# Sheet1.net
KiCad netlist of a schematic drawn in Altium Designer
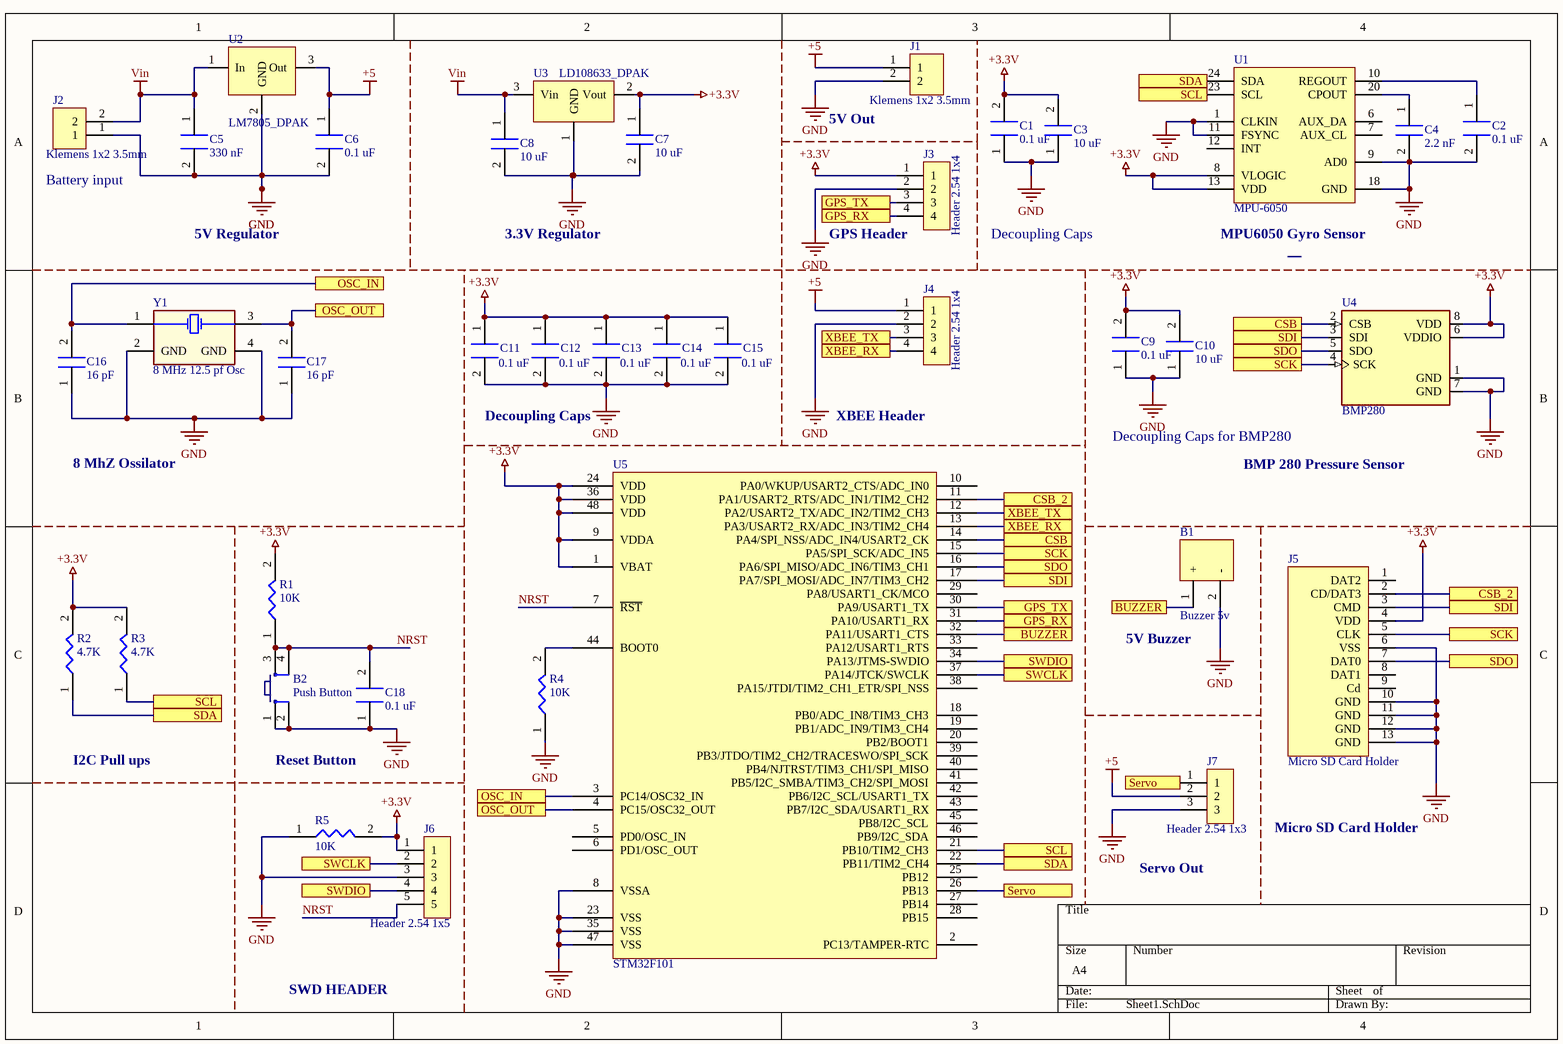
[diagram p0: Sheet1.SchDoc]

(export (version "E")
  (design (tool "Eeschema 10.0.6"))
  (components
    (comp (ref "B1")
      (value "Buzzer 5v")
      (footprint "BUZZER_5V")
      (libsource (lib "Schlib1") (part "Buzzer 5v"))
    )
    (comp (ref "B2")
      (value "Push Button")
      (footprint "PUSB BUTTON-SMD")
      (description "Smd Push Button")
      (libsource (lib "Schlib1") (part "Push Button"))
    )
    (comp (ref "C1")
      (value "0.1 uF")
      (footprint "C1206")
      (description "0.1 uF C1206")
      (libsource (lib "Schlib1") (part "0.1 uF C1206"))
    )
    (comp (ref "C2")
      (value "0.1 uF")
      (footprint "C1206")
      (description "0.1 uF C1206")
      (libsource (lib "Schlib1") (part "0.1 uF C1206"))
    )
    (comp (ref "C3") (value "10 uF") (footprint "C1206") (libsource (lib "Schlib1") (part "10 uF")))
    (comp (ref "C4")
      (value "2.2 nF")
      (footprint "C1206")
      (description "2.2 nF c1206")
      (libsource (lib "Schlib1") (part "2.2 nF c1206"))
    )
    (comp (ref "C5")
      (value "330 nF")
      (footprint "C1206")
      (description "330 nF C1206")
      (libsource (lib "Schlib1") (part "330 nF C1206"))
    )
    (comp (ref "C6")
      (value "0.1 uF")
      (footprint "C1206")
      (description "0.1 uF C1206")
      (libsource (lib "Schlib1") (part "0.1 uF C1206"))
    )
    (comp (ref "C7") (value "10 uF") (footprint "C1206") (libsource (lib "Schlib1") (part "10 uF")))
    (comp (ref "C8") (value "10 uF") (footprint "C1206") (libsource (lib "Schlib1") (part "10 uF")))
    (comp (ref "C9")
      (value "0.1 uF")
      (footprint "C1206")
      (description "0.1 uF C1206")
      (libsource (lib "Schlib1") (part "0.1 uF C1206"))
    )
    (comp (ref "C10") (value "10 uF") (footprint "C1206") (libsource (lib "Schlib1") (part "10 uF")))
    (comp (ref "C11")
      (value "0.1 uF")
      (footprint "C1206")
      (description "0.1 uF C1206")
      (libsource (lib "Schlib1") (part "0.1 uF C1206"))
    )
    (comp (ref "C12")
      (value "0.1 uF")
      (footprint "C1206")
      (description "0.1 uF C1206")
      (libsource (lib "Schlib1") (part "0.1 uF C1206"))
    )
    (comp (ref "C13")
      (value "0.1 uF")
      (footprint "C1206")
      (description "0.1 uF C1206")
      (libsource (lib "Schlib1") (part "0.1 uF C1206"))
    )
    (comp (ref "C14")
      (value "0.1 uF")
      (footprint "C1206")
      (description "0.1 uF C1206")
      (libsource (lib "Schlib1") (part "0.1 uF C1206"))
    )
    (comp (ref "C15")
      (value "0.1 uF")
      (footprint "C1206")
      (description "0.1 uF C1206")
      (libsource (lib "Schlib1") (part "0.1 uF C1206"))
    )
    (comp (ref "C16") (value "16 pF") (footprint "C1206") (libsource (lib "Schlib1") (part "16 pF")))
    (comp (ref "C17") (value "16 pF") (footprint "C1206") (libsource (lib "Schlib1") (part "16 pF")))
    (comp (ref "C18")
      (value "0.1 uF")
      (footprint "C1206")
      (description "0.1 uF C1206")
      (libsource (lib "Schlib1") (part "0.1 uF C1206"))
    )
    (comp (ref "J1")
      (value "Klemens 1x2 3.5mm")
      (footprint "Klemens 1x2 - 3.5mm")
      (libsource (lib "") (part "Klemens 1x2 3.5mm_1"))
    )
    (comp (ref "J2")
      (value "Klemens 1x2 3.5mm")
      (footprint "Klemens 1x2 - 3.5mm")
      (libsource (lib "Schlib1") (part "Klemens 1x2 3.5mm"))
    )
    (comp (ref "J3")
      (value "Header 2.54 1x4")
      (footprint "Header 2.54 1x4")
      (libsource (lib "Schlib1") (part "Header 2.54 1x4"))
    )
    (comp (ref "J4")
      (value "Header 2.54 1x4")
      (footprint "Header 2.54 1x4")
      (libsource (lib "Schlib1") (part "Header 2.54 1x4"))
    )
    (comp (ref "J5")
      (value "Micro SD Card Holder")
      (footprint "Micro SD Card Holder")
      (libsource (lib "Schlib1") (part "Micro SD Card Holder"))
    )
    (comp (ref "J6")
      (value "Header 2.54 1x5")
      (footprint "Header 2.54 1x5")
      (libsource (lib "Schlib1") (part "Header 2.54 1x5"))
    )
    (comp (ref "J7")
      (value "Header 2.54 1x3")
      (footprint "Header 2.54 1x3")
      (libsource (lib "Schlib1") (part "Header 2.54 1x3"))
    )
    (comp (ref "R1")
      (value "10K")
      (footprint "R1206 Resıstor")
      (description "10K R1206")
      (libsource (lib "Schlib1") (part "10K R1206"))
    )
    (comp (ref "R2")
      (value "4.7K")
      (footprint "R1206 Resıstor")
      (description "4.7K R1206")
      (libsource (lib "Schlib1") (part "4.7K R1206"))
    )
    (comp (ref "R3")
      (value "4.7K")
      (footprint "R1206 Resıstor")
      (description "4.7K R1206")
      (libsource (lib "Schlib1") (part "4.7K R1206"))
    )
    (comp (ref "R4")
      (value "10K")
      (footprint "R1206 Resıstor")
      (description "10K R1206")
      (libsource (lib "Schlib1") (part "10K R1206"))
    )
    (comp (ref "R5")
      (value "10K")
      (footprint "R1206 Resıstor")
      (description "10K R1206")
      (libsource (lib "Schlib1") (part "10K R1206"))
    )
    (comp (ref "U1")
      (value "MPU-6050")
      (footprint "QFN50P400X400X90_HS-25N")
      (libsource (lib "Schlib1") (part "MPU-6050"))
    )
    (comp (ref "U2")
      (value "LM7805_DPAK")
      (footprint "DPAK_3D")
      (libsource (lib "Schlib1") (part "LM7805_DPAK"))
    )
    (comp (ref "U3")
      (value "LD108633_DPAK")
      (footprint "DPAK_3D")
      (libsource (lib "Schlib1") (part "LD108633_DPAK"))
    )
    (comp (ref "U4") (value "BMP280") (footprint "BMP280") (libsource (lib "Schlib1") (part "BMP280")))
    (comp (ref "U5")
      (value "STM32F101")
      (footprint "LQFP48_stm32")
      (libsource (lib "Schlib1") (part "STM32F101"))
    )
    (comp (ref "Y1")
      (value "8 MHz 12.5 pf Osc")
      (footprint "8 MHZ Osc.")
      (libsource (lib "Schlib1") (part "8 MHz 12.5 pf Osc"))
    )
  )
  (nets
    (net (code "1") (name "+3.3V") (class "Default")
      (node (ref "C1") (pin "2") (pinfunction "2_2") (pintype "passive"))
      (node (ref "C10") (pin "2") (pinfunction "2_2") (pintype "passive"))
      (node (ref "C11") (pin "1") (pinfunction "1_1") (pintype "passive"))
      (node (ref "C12") (pin "1") (pinfunction "1_1") (pintype "passive"))
      (node (ref "C13") (pin "1") (pinfunction "1_1") (pintype "passive"))
      (node (ref "C14") (pin "1") (pinfunction "1_1") (pintype "passive"))
      (node (ref "C15") (pin "1") (pinfunction "1_1") (pintype "passive"))
      (node (ref "C3") (pin "2") (pinfunction "2_2") (pintype "passive"))
      (node (ref "C7") (pin "1") (pinfunction "1_1") (pintype "passive"))
      (node (ref "C9") (pin "2") (pinfunction "2_2") (pintype "passive"))
      (node (ref "J3") (pin "1") (pinfunction "1_1") (pintype "passive"))
      (node (ref "J5") (pin "4") (pinfunction "VDD_4") (pintype "passive"))
      (node (ref "J6") (pin "1") (pinfunction "1_1") (pintype "passive"))
      (node (ref "R1") (pin "2") (pinfunction "2_2") (pintype "passive"))
      (node (ref "R2") (pin "2") (pinfunction "2_2") (pintype "passive"))
      (node (ref "R3") (pin "2") (pinfunction "2_2") (pintype "passive"))
      (node (ref "R5") (pin "2") (pinfunction "2_2") (pintype "passive"))
      (node (ref "U1") (pin "13") (pinfunction "VDD_13") (pintype "passive"))
      (node (ref "U1") (pin "8") (pinfunction "VLOGIC_8") (pintype "passive"))
      (node (ref "U3") (pin "2") (pinfunction "Vout_2") (pintype "passive"))
      (node (ref "U4") (pin "6") (pinfunction "VDDIO_6") (pintype "power_in"))
      (node (ref "U4") (pin "8") (pinfunction "VDD_8") (pintype "power_in"))
      (node (ref "U5") (pin "1") (pinfunction "VBAT_1") (pintype "passive"))
      (node (ref "U5") (pin "24") (pinfunction "VDD_24") (pintype "passive"))
      (node (ref "U5") (pin "36") (pinfunction "VDD_36") (pintype "passive"))
      (node (ref "U5") (pin "48") (pinfunction "VDD_48") (pintype "passive"))
      (node (ref "U5") (pin "9") (pinfunction "VDDA_9") (pintype "passive"))
    )
    (net (code "2") (name "+5") (class "Default")
      (node (ref "C6") (pin "1") (pinfunction "1_1") (pintype "passive"))
      (node (ref "J1") (pin "1") (pinfunction "1_1") (pintype "passive"))
      (node (ref "J4") (pin "1") (pinfunction "1_1") (pintype "passive"))
      (node (ref "J7") (pin "2") (pinfunction "2_2") (pintype "passive"))
      (node (ref "U2") (pin "3") (pinfunction "Out_3") (pintype "passive"))
    )
    (net (code "3") (name "/BUZZER") (class "Default")
      (node (ref "B1") (pin "1") (pinfunction "+_1") (pintype "passive"))
      (node (ref "U5") (pin "32") (pinfunction "PA11/USART1_CTS_32") (pintype "passive"))
    )
    (net (code "4") (name "/CSB") (class "Default")
      (node (ref "U4") (pin "2") (pinfunction "CSB_2") (pintype "input"))
      (node (ref "U5") (pin "14") (pinfunction "PA4/SPI_NSS/ADC_IN4/USART2_CK_14") (pintype "passive"))
    )
    (net (code "5") (name "/CSB_2") (class "Default")
      (node (ref "J5") (pin "2") (pinfunction "CD/DAT3_2") (pintype "passive"))
      (node (ref "U5") (pin "11") (pinfunction "PA1/USART2_RTS/ADC_IN1/TIM2_CH2_11") (pintype "passive"))
    )
    (net (code "6") (name "/GPS_RX") (class "Default")
      (node (ref "J3") (pin "4") (pinfunction "4_4") (pintype "passive"))
      (node (ref "U5") (pin "31") (pinfunction "PA10/USART1_RX_31") (pintype "passive"))
    )
    (net (code "7") (name "/GPS_TX") (class "Default")
      (node (ref "J3") (pin "3") (pinfunction "3_3") (pintype "passive"))
      (node (ref "U5") (pin "30") (pinfunction "PA9/USART1_TX_30") (pintype "passive"))
    )
    (net (code "8") (name "/NRST") (class "Default")
      (node (ref "B2") (pin "3") (pinfunction "3_3") (pintype "passive"))
      (node (ref "B2") (pin "4") (pinfunction "4_4") (pintype "passive"))
      (node (ref "C18") (pin "2") (pinfunction "2_2") (pintype "passive"))
      (node (ref "J6") (pin "5") (pinfunction "5_5") (pintype "passive"))
      (node (ref "R1") (pin "1") (pinfunction "1_1") (pintype "passive"))
      (node (ref "U5") (pin "7") (pinfunction "~{RST}_7") (pintype "passive"))
    )
    (net (code "9") (name "/OSC_IN") (class "Default")
      (node (ref "C16") (pin "2") (pinfunction "2_2") (pintype "passive"))
      (node (ref "U5") (pin "3") (pinfunction "PC14/OSC32_IN_3") (pintype "passive"))
      (node (ref "Y1") (pin "1") (pintype "power_in"))
    )
    (net (code "10") (name "/OSC_OUT") (class "Default")
      (node (ref "C17") (pin "2") (pinfunction "2_2") (pintype "passive"))
      (node (ref "U5") (pin "4") (pinfunction "PC15/OSC32_OUT_4") (pintype "passive"))
      (node (ref "Y1") (pin "3") (pintype "passive"))
    )
    (net (code "11") (name "/SCK") (class "Default")
      (node (ref "J5") (pin "5") (pinfunction "CLK_5") (pintype "passive"))
      (node (ref "U4") (pin "4") (pinfunction "SCK_4") (pintype "input"))
      (node (ref "U5") (pin "15") (pinfunction "PA5/SPI_SCK/ADC_IN5_15") (pintype "passive"))
    )
    (net (code "12") (name "/SCL") (class "Default")
      (node (ref "R3") (pin "1") (pinfunction "1_1") (pintype "passive"))
      (node (ref "U1") (pin "23") (pinfunction "SCL_23") (pintype "passive"))
      (node (ref "U5") (pin "21") (pinfunction "PB10/TIM2_CH3_21") (pintype "passive"))
    )
    (net (code "13") (name "/SDA") (class "Default")
      (node (ref "R2") (pin "1") (pinfunction "1_1") (pintype "passive"))
      (node (ref "U1") (pin "24") (pinfunction "SDA_24") (pintype "passive"))
      (node (ref "U5") (pin "22") (pinfunction "PB11/TIM2_CH4_22") (pintype "passive"))
    )
    (net (code "14") (name "/SDI") (class "Default")
      (node (ref "J5") (pin "3") (pinfunction "CMD_3") (pintype "passive"))
      (node (ref "U4") (pin "3") (pinfunction "SDI_3") (pintype "bidirectional"))
      (node (ref "U5") (pin "17") (pinfunction "PA7/SPI_MOSI/ADC_IN7/TIM3_CH2_17") (pintype "passive"))
    )
    (net (code "15") (name "/SDO") (class "Default")
      (node (ref "J5") (pin "7") (pinfunction "DAT0_7") (pintype "passive"))
      (node (ref "U4") (pin "5") (pinfunction "SDO_5") (pintype "bidirectional"))
      (node (ref "U5") (pin "16") (pinfunction "PA6/SPI_MISO/ADC_IN6/TIM3_CH1_16") (pintype "passive"))
    )
    (net (code "16") (name "/SWCLK") (class "Default")
      (node (ref "J6") (pin "2") (pinfunction "2_2") (pintype "passive"))
      (node (ref "U5") (pin "37") (pinfunction "PA14/JTCK/SWCLK_37") (pintype "passive"))
    )
    (net (code "17") (name "/SWDIO") (class "Default")
      (node (ref "J6") (pin "4") (pinfunction "4_4") (pintype "passive"))
      (node (ref "U5") (pin "34") (pinfunction "PA13/JTMS-SWDIO_34") (pintype "passive"))
    )
    (net (code "18") (name "/Servo") (class "Default")
      (node (ref "J7") (pin "1") (pinfunction "1_1") (pintype "passive"))
      (node (ref "U5") (pin "26") (pinfunction "PB13_26") (pintype "passive"))
    )
    (net (code "19") (name "/XBEE_RX") (class "Default")
      (node (ref "J4") (pin "4") (pinfunction "4_4") (pintype "passive"))
      (node (ref "U5") (pin "13") (pinfunction "PA3/USART2_RX/ADC_IN3/TIM2_CH4_13") (pintype "passive"))
    )
    (net (code "20") (name "/XBEE_TX") (class "Default")
      (node (ref "J4") (pin "3") (pinfunction "3_3") (pintype "passive"))
      (node (ref "U5") (pin "12") (pinfunction "PA2/USART2_TX/ADC_IN2/TIM2_CH3_12") (pintype "passive"))
    )
    (net (code "21") (name "GND") (class "Default")
      (node (ref "B1") (pin "2") (pinfunction "-_2") (pintype "passive"))
      (node (ref "B2") (pin "1") (pinfunction "1_1") (pintype "passive"))
      (node (ref "B2") (pin "2") (pinfunction "2_2") (pintype "passive"))
      (node (ref "C1") (pin "1") (pinfunction "1_1") (pintype "passive"))
      (node (ref "C10") (pin "1") (pinfunction "1_1") (pintype "passive"))
      (node (ref "C11") (pin "2") (pinfunction "2_2") (pintype "passive"))
      (node (ref "C12") (pin "2") (pinfunction "2_2") (pintype "passive"))
      (node (ref "C13") (pin "2") (pinfunction "2_2") (pintype "passive"))
      (node (ref "C14") (pin "2") (pinfunction "2_2") (pintype "passive"))
      (node (ref "C15") (pin "2") (pinfunction "2_2") (pintype "passive"))
      (node (ref "C16") (pin "1") (pinfunction "1_1") (pintype "passive"))
      (node (ref "C17") (pin "1") (pinfunction "1_1") (pintype "passive"))
      (node (ref "C18") (pin "1") (pinfunction "1_1") (pintype "passive"))
      (node (ref "C2") (pin "2") (pinfunction "2_2") (pintype "passive"))
      (node (ref "C3") (pin "1") (pinfunction "1_1") (pintype "passive"))
      (node (ref "C4") (pin "2") (pinfunction "2_2") (pintype "passive"))
      (node (ref "C5") (pin "2") (pinfunction "2_2") (pintype "passive"))
      (node (ref "C6") (pin "2") (pinfunction "2_2") (pintype "passive"))
      (node (ref "C7") (pin "2") (pinfunction "2_2") (pintype "passive"))
      (node (ref "C8") (pin "2") (pinfunction "2_2") (pintype "passive"))
      (node (ref "C9") (pin "1") (pinfunction "1_1") (pintype "passive"))
      (node (ref "J1") (pin "2") (pinfunction "2_2") (pintype "passive"))
      (node (ref "J2") (pin "1") (pinfunction "1_1") (pintype "passive"))
      (node (ref "J3") (pin "2") (pinfunction "2_2") (pintype "passive"))
      (node (ref "J4") (pin "2") (pinfunction "2_2") (pintype "passive"))
      (node (ref "J5") (pin "10") (pinfunction "GND_10") (pintype "passive"))
      (node (ref "J5") (pin "11") (pinfunction "GND_11") (pintype "passive"))
      (node (ref "J5") (pin "12") (pinfunction "GND_12") (pintype "passive"))
      (node (ref "J5") (pin "13") (pinfunction "GND_13") (pintype "passive"))
      (node (ref "J5") (pin "6") (pinfunction "VSS_6") (pintype "passive"))
      (node (ref "J6") (pin "3") (pinfunction "3_3") (pintype "passive"))
      (node (ref "J7") (pin "3") (pinfunction "3_3") (pintype "passive"))
      (node (ref "R4") (pin "1") (pinfunction "1_1") (pintype "passive"))
      (node (ref "R5") (pin "1") (pinfunction "1_1") (pintype "passive"))
      (node (ref "U1") (pin "1") (pinfunction "CLKIN_1") (pintype "passive"))
      (node (ref "U1") (pin "11") (pinfunction "FSYNC_11") (pintype "passive"))
      (node (ref "U1") (pin "18") (pinfunction "GND_18") (pintype "passive"))
      (node (ref "U1") (pin "9") (pinfunction "AD0_9") (pintype "passive"))
      (node (ref "U2") (pin "2") (pinfunction "GND_2") (pintype "passive"))
      (node (ref "U3") (pin "1") (pinfunction "GND_1") (pintype "passive"))
      (node (ref "U4") (pin "1") (pinfunction "GND_1") (pintype "power_in"))
      (node (ref "U4") (pin "7") (pinfunction "GND_7") (pintype "power_in"))
      (node (ref "U5") (pin "23") (pinfunction "VSS_23") (pintype "passive"))
      (node (ref "U5") (pin "35") (pinfunction "VSS_35") (pintype "passive"))
      (node (ref "U5") (pin "47") (pinfunction "VSS_47") (pintype "passive"))
      (node (ref "U5") (pin "8") (pinfunction "VSSA_8") (pintype "passive"))
      (node (ref "Y1") (pin "2") (pinfunction "GND_2") (pintype "power_in"))
      (node (ref "Y1") (pin "4") (pinfunction "GND_4") (pintype "passive"))
    )
    (net (code "22") (name "Net-(U1-CPOUT)") (class "Default")
      (node (ref "C4") (pin "1") (pinfunction "1_1") (pintype "passive"))
      (node (ref "U1") (pin "20") (pinfunction "CPOUT_20") (pintype "passive"))
    )
    (net (code "23") (name "Net-(U1-REGOUT)") (class "Default")
      (node (ref "C2") (pin "1") (pinfunction "1_1") (pintype "passive"))
      (node (ref "U1") (pin "10") (pinfunction "REGOUT_10") (pintype "passive"))
    )
    (net (code "24") (name "Net-(U5-BOOT0)") (class "Default")
      (node (ref "R4") (pin "2") (pinfunction "2_2") (pintype "passive"))
      (node (ref "U5") (pin "44") (pinfunction "BOOT0_44") (pintype "passive"))
    )
    (net (code "25") (name "Vin") (class "Default")
      (node (ref "C5") (pin "1") (pinfunction "1_1") (pintype "passive"))
      (node (ref "C8") (pin "1") (pinfunction "1_1") (pintype "passive"))
      (node (ref "J2") (pin "2") (pinfunction "2_2") (pintype "passive"))
      (node (ref "U2") (pin "1") (pinfunction "In_1") (pintype "passive"))
      (node (ref "U3") (pin "3") (pinfunction "Vin_3") (pintype "passive"))
    )
    (net (code "26") (name "unconnected-(J5-Cd-Pad9)") (class "Default")
      (node (ref "J5") (pin "9") (pinfunction "Cd_9") (pintype "passive"))
    )
    (net (code "27") (name "unconnected-(J5-DAT1-Pad8)") (class "Default")
      (node (ref "J5") (pin "8") (pinfunction "DAT1_8") (pintype "passive"))
    )
    (net (code "28") (name "unconnected-(J5-DAT2-Pad1)") (class "Default")
      (node (ref "J5") (pin "1") (pinfunction "DAT2_1") (pintype "passive"))
    )
    (net (code "29") (name "unconnected-(U1-AUX_CL-Pad7)") (class "Default")
      (node (ref "U1") (pin "7") (pinfunction "AUX_CL_7") (pintype "passive"))
    )
    (net (code "30") (name "unconnected-(U1-AUX_DA-Pad6)") (class "Default")
      (node (ref "U1") (pin "6") (pinfunction "AUX_DA_6") (pintype "passive"))
    )
    (net (code "31") (name "unconnected-(U1-INT-Pad12)") (class "Default")
      (node (ref "U1") (pin "12") (pinfunction "INT_12") (pintype "passive"))
    )
    (net (code "32") (name "unconnected-(U5-PA0{slash}WKUP{slash}USART2_CTS{slash}ADC_IN0-Pad10)") (class "Default")
      (node (ref "U5") (pin "10") (pinfunction "PA0/WKUP/USART2_CTS/ADC_IN0_10") (pintype "passive"))
    )
    (net (code "33") (name "unconnected-(U5-PA8{slash}USART1_CK{slash}MCO-Pad29)") (class "Default")
      (node (ref "U5") (pin "29") (pinfunction "PA8/USART1_CK/MCO_29") (pintype "passive"))
    )
    (net (code "34") (name "unconnected-(U5-PA12{slash}USART1_RTS-Pad33)") (class "Default")
      (node (ref "U5") (pin "33") (pinfunction "PA12/USART1_RTS_33") (pintype "passive"))
    )
    (net (code "35") (name "unconnected-(U5-PA15{slash}JTDI{slash}TIM2_CH1_ETR{slash}SPI_NSS-Pad38)") (class "Default")
      (node (ref "U5") (pin "38") (pinfunction "PA15/JTDI/TIM2_CH1_ETR/SPI_NSS_38") (pintype "passive"))
    )
    (net (code "36") (name "unconnected-(U5-PB0{slash}ADC_IN8{slash}TIM3_CH3-Pad18)") (class "Default")
      (node (ref "U5") (pin "18") (pinfunction "PB0/ADC_IN8/TIM3_CH3_18") (pintype "passive"))
    )
    (net (code "37") (name "unconnected-(U5-PB1{slash}ADC_IN9{slash}TIM3_CH4-Pad19)") (class "Default")
      (node (ref "U5") (pin "19") (pinfunction "PB1/ADC_IN9/TIM3_CH4_19") (pintype "passive"))
    )
    (net (code "38") (name "unconnected-(U5-PB2{slash}BOOT1-Pad20)") (class "Default")
      (node (ref "U5") (pin "20") (pinfunction "PB2/BOOT1_20") (pintype "passive"))
    )
    (net (code "39") (name "unconnected-(U5-PB3{slash}JTDO{slash}TIM2_CH2{slash}TRACESWO{slash}SPI_SCK-Pad39)") (class "Default")
      (node (ref "U5") (pin "39") (pinfunction "PB3/JTDO/TIM2_CH2/TRACESWO/SPI_SCK_39") (pintype "passive"))
    )
    (net (code "40") (name "unconnected-(U5-PB4{slash}NJTRST{slash}TIM3_CH1{slash}SPI_MISO-Pad40)") (class "Default")
      (node (ref "U5") (pin "40") (pinfunction "PB4/NJTRST/TIM3_CH1/SPI_MISO_40") (pintype "passive"))
    )
    (net (code "41") (name "unconnected-(U5-PB5{slash}I2C_SMBA{slash}TIM3_CH2{slash}SPI_MOSI-Pad41)") (class "Default")
      (node (ref "U5") (pin "41") (pinfunction "PB5/I2C_SMBA/TIM3_CH2/SPI_MOSI_41") (pintype "passive"))
    )
    (net (code "42") (name "unconnected-(U5-PB6{slash}I2C_SCL{slash}USART1_TX-Pad42)") (class "Default")
      (node (ref "U5") (pin "42") (pinfunction "PB6/I2C_SCL/USART1_TX_42") (pintype "passive"))
    )
    (net (code "43") (name "unconnected-(U5-PB7{slash}I2C_SDA{slash}USART1_RX-Pad43)") (class "Default")
      (node (ref "U5") (pin "43") (pinfunction "PB7/I2C_SDA/USART1_RX_43") (pintype "passive"))
    )
    (net (code "44") (name "unconnected-(U5-PB8{slash}I2C_SCL-Pad45)") (class "Default")
      (node (ref "U5") (pin "45") (pinfunction "PB8/I2C_SCL_45") (pintype "passive"))
    )
    (net (code "45") (name "unconnected-(U5-PB9{slash}I2C_SDA-Pad46)") (class "Default")
      (node (ref "U5") (pin "46") (pinfunction "PB9/I2C_SDA_46") (pintype "passive"))
    )
    (net (code "46") (name "unconnected-(U5-PB12-Pad25)") (class "Default")
      (node (ref "U5") (pin "25") (pinfunction "PB12_25") (pintype "passive"))
    )
    (net (code "47") (name "unconnected-(U5-PB14-Pad27)") (class "Default")
      (node (ref "U5") (pin "27") (pinfunction "PB14_27") (pintype "passive"))
    )
    (net (code "48") (name "unconnected-(U5-PB15-Pad28)") (class "Default")
      (node (ref "U5") (pin "28") (pinfunction "PB15_28") (pintype "passive"))
    )
    (net (code "49") (name "unconnected-(U5-PC13{slash}TAMPER-RTC-Pad2)") (class "Default")
      (node (ref "U5") (pin "2") (pinfunction "PC13/TAMPER-RTC_2") (pintype "passive"))
    )
    (net (code "50") (name "unconnected-(U5-PD0{slash}OSC_IN-Pad5)") (class "Default")
      (node (ref "U5") (pin "5") (pinfunction "PD0/OSC_IN_5") (pintype "passive"))
    )
    (net (code "51") (name "unconnected-(U5-PD1{slash}OSC_OUT-Pad6)") (class "Default")
      (node (ref "U5") (pin "6") (pinfunction "PD1/OSC_OUT_6") (pintype "passive"))
    )
  )
)
